# lcd1602a-connector.net
KiCad netlist of a schematic drawn in EAGLE
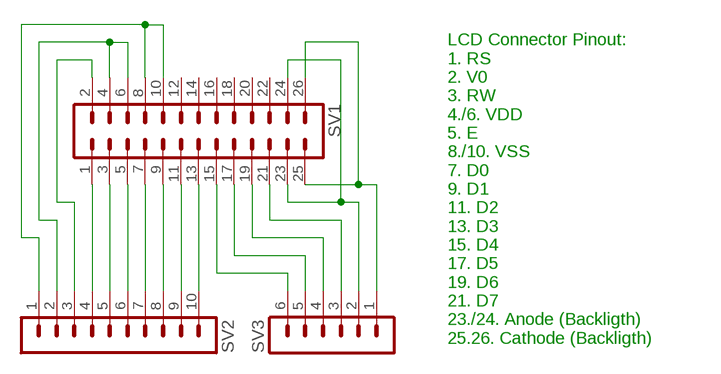
[diagram p0: schematic, sheet 1]

(export (version "E")
  (design (tool "Eeschema 10.0.6"))
  (components
    (comp (ref "SV1")
      (value "ML26")
      (footprint "eagle-import:ML26")
      (libsource (lib "eagle-import") (part "ML26"))
    )
    (comp (ref "SV2")
      (value "MA10-1")
      (footprint "eagle-import:MA10-1")
      (libsource (lib "eagle-import") (part "MA10-1"))
    )
    (comp (ref "SV3")
      (value "MA06-1")
      (footprint "eagle-import:MA06-1")
      (libsource (lib "eagle-import") (part "MA06-1"))
    )
  )
  (nets
    (net (code "1") (name "Net-(SV1-Pad1)") (class "Default")
      (node (ref "SV1") (pin "1") (pinfunction "1_1") (pintype "passive"))
      (node (ref "SV2") (pin "4") (pinfunction "4_4") (pintype "passive"))
    )
    (net (code "2") (name "Net-(SV1-Pad2)") (class "Default")
      (node (ref "SV1") (pin "2") (pinfunction "2_2") (pintype "passive"))
      (node (ref "SV2") (pin "3") (pinfunction "3_3") (pintype "passive"))
    )
    (net (code "3") (name "Net-(SV1-Pad3)") (class "Default")
      (node (ref "SV1") (pin "3") (pinfunction "3_3") (pintype "passive"))
      (node (ref "SV2") (pin "5") (pinfunction "5_5") (pintype "passive"))
    )
    (net (code "4") (name "Net-(SV1-Pad4)") (class "Default")
      (node (ref "SV1") (pin "4") (pinfunction "4_4") (pintype "passive"))
      (node (ref "SV1") (pin "6") (pinfunction "6_6") (pintype "passive"))
      (node (ref "SV2") (pin "2") (pinfunction "2_2") (pintype "passive"))
    )
    (net (code "5") (name "Net-(SV1-Pad5)") (class "Default")
      (node (ref "SV1") (pin "5") (pinfunction "5_5") (pintype "passive"))
      (node (ref "SV2") (pin "6") (pinfunction "6_6") (pintype "passive"))
    )
    (net (code "6") (name "Net-(SV1-Pad7)") (class "Default")
      (node (ref "SV1") (pin "7") (pinfunction "7_7") (pintype "passive"))
      (node (ref "SV2") (pin "7") (pinfunction "7_7") (pintype "passive"))
    )
    (net (code "7") (name "Net-(SV1-Pad9)") (class "Default")
      (node (ref "SV1") (pin "9") (pinfunction "9_9") (pintype "passive"))
      (node (ref "SV2") (pin "8") (pinfunction "8_8") (pintype "passive"))
    )
    (net (code "8") (name "Net-(SV1-Pad10)") (class "Default")
      (node (ref "SV1") (pin "10") (pinfunction "10_10") (pintype "passive"))
      (node (ref "SV1") (pin "8") (pinfunction "8_8") (pintype "passive"))
      (node (ref "SV2") (pin "1") (pinfunction "1_1") (pintype "passive"))
    )
    (net (code "9") (name "Net-(SV1-Pad11)") (class "Default")
      (node (ref "SV1") (pin "11") (pinfunction "11_11") (pintype "passive"))
      (node (ref "SV2") (pin "9") (pinfunction "9_9") (pintype "passive"))
    )
    (net (code "10") (name "Net-(SV1-Pad13)") (class "Default")
      (node (ref "SV1") (pin "13") (pinfunction "13_13") (pintype "passive"))
      (node (ref "SV2") (pin "10") (pinfunction "10_10") (pintype "passive"))
    )
    (net (code "11") (name "Net-(SV1-Pad15)") (class "Default")
      (node (ref "SV1") (pin "15") (pinfunction "15_15") (pintype "passive"))
      (node (ref "SV3") (pin "6") (pinfunction "6_6") (pintype "passive"))
    )
    (net (code "12") (name "Net-(SV1-Pad17)") (class "Default")
      (node (ref "SV1") (pin "17") (pinfunction "17_17") (pintype "passive"))
      (node (ref "SV3") (pin "5") (pinfunction "5_5") (pintype "passive"))
    )
    (net (code "13") (name "Net-(SV1-Pad19)") (class "Default")
      (node (ref "SV1") (pin "19") (pinfunction "19_19") (pintype "passive"))
      (node (ref "SV3") (pin "4") (pinfunction "4_4") (pintype "passive"))
    )
    (net (code "14") (name "Net-(SV1-Pad21)") (class "Default")
      (node (ref "SV1") (pin "21") (pinfunction "21_21") (pintype "passive"))
      (node (ref "SV3") (pin "3") (pinfunction "3_3") (pintype "passive"))
    )
    (net (code "15") (name "Net-(SV1-Pad23)") (class "Default")
      (node (ref "SV1") (pin "23") (pinfunction "23_23") (pintype "passive"))
      (node (ref "SV1") (pin "24") (pinfunction "24_24") (pintype "passive"))
      (node (ref "SV3") (pin "2") (pinfunction "2_2") (pintype "passive"))
    )
    (net (code "16") (name "Net-(SV1-Pad25)") (class "Default")
      (node (ref "SV1") (pin "25") (pinfunction "25_25") (pintype "passive"))
      (node (ref "SV1") (pin "26") (pinfunction "26_26") (pintype "passive"))
      (node (ref "SV3") (pin "1") (pinfunction "1_1") (pintype "passive"))
    )
    (net (code "17") (name "unconnected-(SV1-Pad12)") (class "Default")
      (node (ref "SV1") (pin "12") (pinfunction "12_12") (pintype "passive"))
    )
    (net (code "18") (name "unconnected-(SV1-Pad14)") (class "Default")
      (node (ref "SV1") (pin "14") (pinfunction "14_14") (pintype "passive"))
    )
    (net (code "19") (name "unconnected-(SV1-Pad16)") (class "Default")
      (node (ref "SV1") (pin "16") (pinfunction "16_16") (pintype "passive"))
    )
    (net (code "20") (name "unconnected-(SV1-Pad18)") (class "Default")
      (node (ref "SV1") (pin "18") (pinfunction "18_18") (pintype "passive"))
    )
    (net (code "21") (name "unconnected-(SV1-Pad20)") (class "Default")
      (node (ref "SV1") (pin "20") (pinfunction "20_20") (pintype "passive"))
    )
    (net (code "22") (name "unconnected-(SV1-Pad22)") (class "Default")
      (node (ref "SV1") (pin "22") (pinfunction "22_22") (pintype "passive"))
    )
  )
)
